# Sheet3.net
KiCad netlist of a schematic drawn in Altium Designer
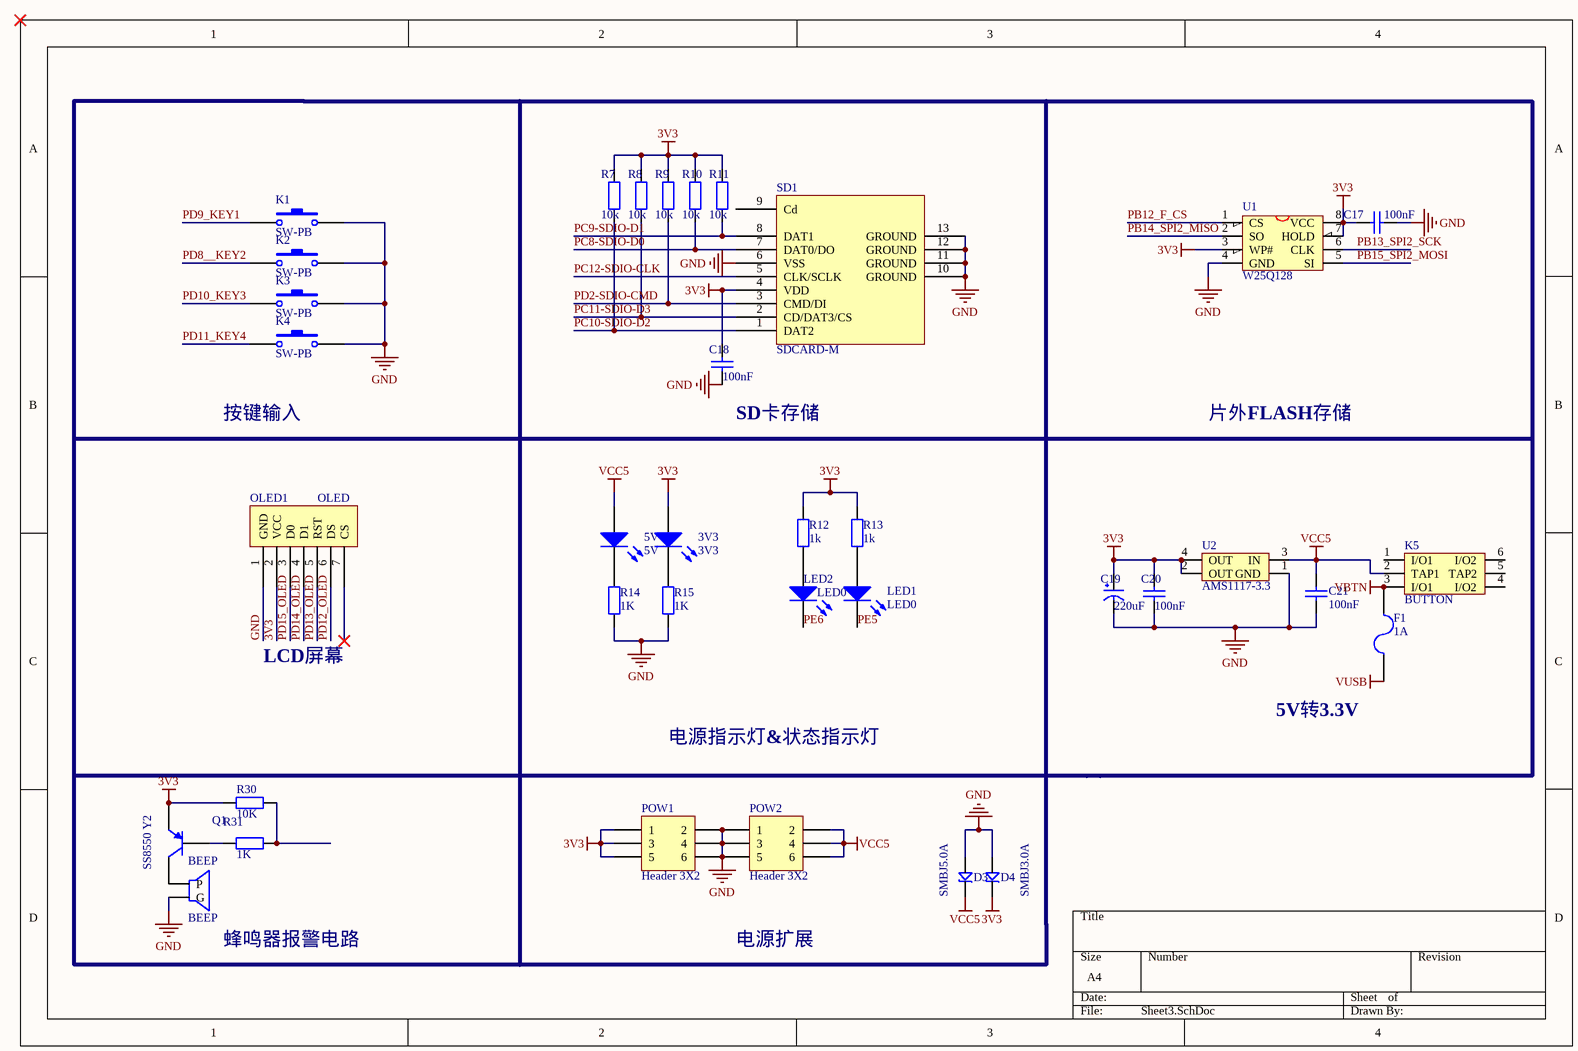
[diagram p0: Sheet3.SchDoc]

(export (version "E")
  (design (tool "Eeschema 10.0.6"))
  (components
    (comp (ref "3V3")
      (value "3V3")
      (footprint "LED_0805")
      (description "Typical INFRARED GaAs LED")
      (fields (field (name "PUBLISHER") "Altium Limited"))
      (libsource (lib "PCB_Project") (part "LED0"))
    )
    (comp (ref "5V")
      (value "5V")
      (footprint "LED_0805")
      (description "Typical INFRARED GaAs LED")
      (fields (field (name "PUBLISHER") "Altium Limited"))
      (libsource (lib "PCB_Project") (part "LED0"))
    )
    (comp (ref "BEEP")
      (value "BEEP")
      (footprint "BUZZER")
      (libsource (lib "Explorer STM32F407封装库") (part "BEEP"))
    )
    (comp (ref "C17")
      (value "100nF")
      (footprint "LC-0603_C")
      (description "无极性电容")
      (fields (field (name "PUBLISHER") "Altium Limited"))
      (libsource (lib "liu_2016") (part "Cap"))
    )
    (comp (ref "C18")
      (value "100nF")
      (footprint "LC-0603_C")
      (description "无极性电容")
      (fields (field (name "PUBLISHER") "Altium Limited"))
      (libsource (lib "liu_2016") (part "Cap"))
    )
    (comp (ref "C19")
      (value "220uF")
      (footprint "CAP_10*10")
      (libsource (lib "Explorer STM32F407封装库") (part "CAP"))
    )
    (comp (ref "C20")
      (value "100nF")
      (footprint "LC-0603_C")
      (description "无极性电容")
      (fields (field (name "PUBLISHER") "Altium Limited"))
      (libsource (lib "liu_2016") (part "Cap"))
    )
    (comp (ref "C21")
      (value "100nF")
      (footprint "LC-0603_C")
      (description "无极性电容")
      (fields (field (name "PUBLISHER") "Altium Limited"))
      (libsource (lib "liu_2016") (part "Cap"))
    )
    (comp (ref "D3")
      (value "SMBJ5.0A")
      (footprint "D1812")
      (description "TVS")
      (libsource (lib "Explorer STM32F407封装库") (part "SMBJ"))
    )
    (comp (ref "D4")
      (value "SMBJ3.0A")
      (footprint "D1812")
      (description "TVS")
      (libsource (lib "Explorer STM32F407封装库") (part "SMBJ"))
    )
    (comp (ref "F1")
      (value "1A")
      (footprint "LC-1206_R")
      (description "保险丝")
      (fields (field (name "Comment") "Fuse") (field (name "PUBLISHER") "Altium Limited"))
      (libsource (lib "liu_2016") (part "Fuse 2"))
    )
    (comp (ref "K1")
      (value "SW-PB")
      (footprint "SW-SMD1")
      (description "Switch")
      (fields (field (name "PUBLISHER") "Altium Limited"))
      (libsource (lib "PCB_Project") (part "SW-PB"))
    )
    (comp (ref "K2")
      (value "SW-PB")
      (footprint "SW-SMD1")
      (description "Switch")
      (fields (field (name "PUBLISHER") "Altium Limited"))
      (libsource (lib "PCB_Project") (part "SW-PB"))
    )
    (comp (ref "K3")
      (value "SW-PB")
      (footprint "SW-SMD1")
      (description "Switch")
      (fields (field (name "PUBLISHER") "Altium Limited"))
      (libsource (lib "PCB_Project") (part "SW-PB"))
    )
    (comp (ref "K4")
      (value "SW-PB")
      (footprint "SW-SMD1")
      (description "Switch")
      (fields (field (name "PUBLISHER") "Altium Limited"))
      (libsource (lib "PCB_Project") (part "SW-PB"))
    )
    (comp (ref "K5")
      (value "BUTTON")
      (footprint "DPDT")
      (libsource (lib "Explorer STM32F407封装库") (part "BUTTON"))
    )
    (comp (ref "LED1")
      (value "LED0")
      (footprint "LED_0805")
      (description "Typical INFRARED GaAs LED")
      (fields (field (name "PUBLISHER") "Altium Limited"))
      (libsource (lib "PCB_Project") (part "LED0"))
    )
    (comp (ref "LED2")
      (value "LED0")
      (footprint "LED_0805")
      (description "Typical INFRARED GaAs LED")
      (fields (field (name "PUBLISHER") "Altium Limited"))
      (libsource (lib "PCB_Project") (part "LED0"))
    )
    (comp (ref "OLED1")
      (value "OLED")
      (footprint "OLED_096")
      (description "OLED屏幕")
      (libsource (lib "liu_2016") (part "OLED_SPI"))
    )
    (comp (ref "POW1")
      (value "Header 3X2")
      (footprint "HDR2X3")
      (description "Header, 3-Pin, Dual row")
      (fields (field (name "PUBLISHER") "Altium Limited"))
      (libsource (lib "Sparks") (part "Header 3X2"))
    )
    (comp (ref "POW2")
      (value "Header 3X2")
      (footprint "HDR2X3")
      (description "Header, 3-Pin, Dual row")
      (fields (field (name "PUBLISHER") "Altium Limited"))
      (libsource (lib "Sparks") (part "Header 3X2"))
    )
    (comp (ref "Q1")
      (value "SS8550 Y2")
      (footprint "LC-SOT-23(SOT-23-3)")
      (description "三极管")
      (libsource (lib "Miscellaneous Devices LC") (part "SOT-23 SS8550 Y2"))
    )
    (comp (ref "R7")
      (value "10k")
      (footprint "LC-0603_R")
      (description "贴片电阻")
      (fields (field (name "PUBLISHER") "Altium Limited"))
      (libsource (lib "liu_2016") (part "Res1"))
    )
    (comp (ref "R8")
      (value "10k")
      (footprint "LC-0603_R")
      (description "贴片电阻")
      (fields (field (name "PUBLISHER") "Altium Limited"))
      (libsource (lib "liu_2016") (part "Res1"))
    )
    (comp (ref "R9")
      (value "10k")
      (footprint "LC-0603_R")
      (description "贴片电阻")
      (fields (field (name "PUBLISHER") "Altium Limited"))
      (libsource (lib "liu_2016") (part "Res1"))
    )
    (comp (ref "R10")
      (value "10k")
      (footprint "LC-0603_R")
      (description "贴片电阻")
      (fields (field (name "PUBLISHER") "Altium Limited"))
      (libsource (lib "liu_2016") (part "Res1"))
    )
    (comp (ref "R11")
      (value "10k")
      (footprint "LC-0603_R")
      (description "贴片电阻")
      (fields (field (name "PUBLISHER") "Altium Limited"))
      (libsource (lib "liu_2016") (part "Res1"))
    )
    (comp (ref "R12")
      (value "1k")
      (footprint "LC-0603_R")
      (description "贴片电阻")
      (fields (field (name "PUBLISHER") "Altium Limited"))
      (libsource (lib "liu_2016") (part "Res1"))
    )
    (comp (ref "R13")
      (value "1k")
      (footprint "LC-0603_R")
      (description "贴片电阻")
      (fields (field (name "PUBLISHER") "Altium Limited"))
      (libsource (lib "liu_2016") (part "Res1"))
    )
    (comp (ref "R14")
      (value "1K")
      (footprint "LC-0603_R")
      (description "贴片电阻")
      (libsource (lib "") (part "0603 1.1KΩ (1101) 1%_1"))
    )
    (comp (ref "R15")
      (value "1K")
      (footprint "LC-0603_R")
      (description "贴片电阻")
      (libsource (lib "") (part "0603 1.1KΩ (1101) 1%_1"))
    )
    (comp (ref "R30")
      (value "10K")
      (footprint "LC-0603_R")
      (description "贴片电阻")
      (libsource (lib "Miscellaneous Devices LC") (part "0603 1.1KΩ (1101) 1%"))
    )
    (comp (ref "R31")
      (value "1K")
      (footprint "LC-0603_R")
      (description "贴片电阻")
      (libsource (lib "Miscellaneous Devices LC") (part "0603 1.1KΩ (1101) 1%"))
    )
    (comp (ref "SD1")
      (value "SDCARD-M")
      (footprint "TF_CARD")
      (description "TF卡槽")
      (libsource (lib "Fszhang") (part "SDCARD-M"))
    )
    (comp (ref "U1")
      (value "W25Q128")
      (footprint "SOIC-8")
      (description "W25X16;SST25VF016;MX25L1605")
      (libsource (lib "SWUST_PanPan") (part "W25X16"))
    )
    (comp (ref "U2")
      (value "AMS1117-3.3")
      (footprint "SOT-233")
      (libsource (lib "Explorer STM32F407封装库") (part "AMS1117"))
    )
  )
  (nets
    (net (code "1") (name "/PB12_F_CS") (class "Default")
      (node (ref "U1") (pin "1") (pinfunction "CS_1") (pintype "passive"))
    )
    (net (code "2") (name "/PB13_SPI2_SCK") (class "Default")
      (node (ref "U1") (pin "6") (pinfunction "CLK_6") (pintype "passive"))
    )
    (net (code "3") (name "/PB14_SPI2_MISO") (class "Default")
      (node (ref "U1") (pin "2") (pinfunction "SO_2") (pintype "passive"))
    )
    (net (code "4") (name "/PB15_SPI2_MOSI") (class "Default")
      (node (ref "U1") (pin "5") (pinfunction "SI_5") (pintype "passive"))
    )
    (net (code "5") (name "/PC8-SDIO-D0") (class "Default")
      (node (ref "R10") (pin "2") (pinfunction "2_2") (pintype "passive"))
      (node (ref "SD1") (pin "7") (pinfunction "DAT0/DO_7") (pintype "passive"))
    )
    (net (code "6") (name "/PC9-SDIO-D1") (class "Default")
      (node (ref "R11") (pin "2") (pinfunction "2_2") (pintype "passive"))
      (node (ref "SD1") (pin "8") (pinfunction "DAT1_8") (pintype "passive"))
    )
    (net (code "7") (name "/PC10-SDIO-D2") (class "Default")
      (node (ref "R7") (pin "2") (pinfunction "2_2") (pintype "passive"))
      (node (ref "SD1") (pin "1") (pinfunction "DAT2_1") (pintype "passive"))
    )
    (net (code "8") (name "/PC11-SDIO-D3") (class "Default")
      (node (ref "R8") (pin "2") (pinfunction "2_2") (pintype "passive"))
      (node (ref "SD1") (pin "2") (pinfunction "CD/DAT3/CS_2") (pintype "passive"))
    )
    (net (code "9") (name "/PC12-SDIO-CLK") (class "Default")
      (node (ref "SD1") (pin "5") (pinfunction "CLK/SCLK_5") (pintype "passive"))
    )
    (net (code "10") (name "/PD2-SDIO-CMD") (class "Default")
      (node (ref "R9") (pin "2") (pinfunction "2_2") (pintype "passive"))
      (node (ref "SD1") (pin "3") (pinfunction "CMD/DI_3") (pintype "passive"))
    )
    (net (code "11") (name "/PD8__KEY2") (class "Default")
      (node (ref "K2") (pin "1") (pinfunction "1_1") (pintype "passive"))
    )
    (net (code "12") (name "/PD9_KEY1") (class "Default")
      (node (ref "K1") (pin "1") (pinfunction "1_1") (pintype "passive"))
    )
    (net (code "13") (name "/PD10_KEY3") (class "Default")
      (node (ref "K3") (pin "1") (pinfunction "1_1") (pintype "passive"))
    )
    (net (code "14") (name "/PD11_KEY4") (class "Default")
      (node (ref "K4") (pin "1") (pinfunction "1_1") (pintype "passive"))
    )
    (net (code "15") (name "/PD12_OLED") (class "Default")
      (node (ref "OLED1") (pin "6") (pinfunction "DS_6") (pintype "passive"))
    )
    (net (code "16") (name "/PD13_OLED") (class "Default")
      (node (ref "OLED1") (pin "5") (pinfunction "RST_5") (pintype "passive"))
    )
    (net (code "17") (name "/PD14_OLED") (class "Default")
      (node (ref "OLED1") (pin "4") (pinfunction "D1_4") (pintype "passive"))
    )
    (net (code "18") (name "/PD15_OLED") (class "Default")
      (node (ref "OLED1") (pin "3") (pinfunction "D0_3") (pintype "passive"))
    )
    (net (code "19") (name "/PE5") (class "Default")
      (node (ref "LED1") (pin "2") (pinfunction "K_2") (pintype "passive"))
    )
    (net (code "20") (name "/PE6") (class "Default")
      (node (ref "LED2") (pin "2") (pinfunction "K_2") (pintype "passive"))
    )
    (net (code "21") (name "3V3") (class "Default")
      (node (ref "3V3") (pin "1") (pinfunction "A_1") (pintype "passive"))
      (node (ref "C17") (pin "2") (pinfunction "2_2") (pintype "passive"))
      (node (ref "C18") (pin "2") (pinfunction "2_2") (pintype "passive"))
      (node (ref "C19") (pin "1") (pinfunction "VCC_1") (pintype "passive"))
      (node (ref "C20") (pin "2") (pinfunction "2_2") (pintype "passive"))
      (node (ref "D4") (pin "2") (pintype "passive"))
      (node (ref "OLED1") (pin "2") (pinfunction "VCC_2") (pintype "passive"))
      (node (ref "POW1") (pin "1") (pinfunction "1_1") (pintype "passive"))
      (node (ref "POW1") (pin "3") (pinfunction "3_3") (pintype "passive"))
      (node (ref "POW1") (pin "5") (pinfunction "5_5") (pintype "passive"))
      (node (ref "Q1") (pin "2") (pinfunction "E_2") (pintype "passive"))
      (node (ref "R10") (pin "1") (pinfunction "1_1") (pintype "passive"))
      (node (ref "R11") (pin "1") (pinfunction "1_1") (pintype "passive"))
      (node (ref "R12") (pin "1") (pinfunction "1_1") (pintype "passive"))
      (node (ref "R13") (pin "1") (pinfunction "1_1") (pintype "passive"))
      (node (ref "R30") (pin "2") (pinfunction "2_2") (pintype "passive"))
      (node (ref "R7") (pin "1") (pinfunction "1_1") (pintype "passive"))
      (node (ref "R8") (pin "1") (pinfunction "1_1") (pintype "passive"))
      (node (ref "R9") (pin "1") (pinfunction "1_1") (pintype "passive"))
      (node (ref "SD1") (pin "4") (pinfunction "VDD_4") (pintype "passive"))
      (node (ref "U1") (pin "3") (pinfunction "WP#_3") (pintype "passive"))
      (node (ref "U1") (pin "7") (pinfunction "HOLD_7") (pintype "passive"))
      (node (ref "U1") (pin "8") (pinfunction "VCC_8") (pintype "passive"))
      (node (ref "U2") (pin "2") (pinfunction "OUT_2") (pintype "passive"))
      (node (ref "U2") (pin "4") (pinfunction "OUT_4") (pintype "passive"))
    )
    (net (code "22") (name "GND") (class "Default")
      (node (ref "BEEP") (pin "2") (pinfunction "G_2") (pintype "passive"))
      (node (ref "C17") (pin "1") (pinfunction "1_1") (pintype "passive"))
      (node (ref "C18") (pin "1") (pinfunction "1_1") (pintype "passive"))
      (node (ref "C19") (pin "2") (pinfunction "GND_2") (pintype "passive"))
      (node (ref "C20") (pin "1") (pinfunction "1_1") (pintype "passive"))
      (node (ref "C21") (pin "1") (pinfunction "1_1") (pintype "passive"))
      (node (ref "D3") (pin "1") (pintype "passive"))
      (node (ref "D4") (pin "1") (pintype "passive"))
      (node (ref "K1") (pin "2") (pinfunction "2_2") (pintype "passive"))
      (node (ref "K2") (pin "2") (pinfunction "2_2") (pintype "passive"))
      (node (ref "K3") (pin "2") (pinfunction "2_2") (pintype "passive"))
      (node (ref "K4") (pin "2") (pinfunction "2_2") (pintype "passive"))
      (node (ref "OLED1") (pin "1") (pinfunction "GND_1") (pintype "passive"))
      (node (ref "POW1") (pin "2") (pinfunction "2_2") (pintype "passive"))
      (node (ref "POW1") (pin "4") (pinfunction "4_4") (pintype "passive"))
      (node (ref "POW1") (pin "6") (pinfunction "6_6") (pintype "passive"))
      (node (ref "POW2") (pin "1") (pinfunction "1_1") (pintype "passive"))
      (node (ref "POW2") (pin "3") (pinfunction "3_3") (pintype "passive"))
      (node (ref "POW2") (pin "5") (pinfunction "5_5") (pintype "passive"))
      (node (ref "R14") (pin "1") (pinfunction "1_1") (pintype "passive"))
      (node (ref "R15") (pin "1") (pinfunction "1_1") (pintype "passive"))
      (node (ref "SD1") (pin "10") (pinfunction "GROUND_10") (pintype "passive"))
      (node (ref "SD1") (pin "11") (pinfunction "GROUND_11") (pintype "passive"))
      (node (ref "SD1") (pin "12") (pinfunction "GROUND_12") (pintype "passive"))
      (node (ref "SD1") (pin "13") (pinfunction "GROUND_13") (pintype "passive"))
      (node (ref "SD1") (pin "6") (pinfunction "VSS_6") (pintype "passive"))
      (node (ref "U1") (pin "4") (pinfunction "GND_4") (pintype "passive"))
      (node (ref "U2") (pin "1") (pinfunction "GND_1") (pintype "passive"))
    )
    (net (code "23") (name "Net-(3V3-K)") (class "Default")
      (node (ref "3V3") (pin "2") (pinfunction "K_2") (pintype "passive"))
      (node (ref "R15") (pin "2") (pinfunction "2_2") (pintype "passive"))
    )
    (net (code "24") (name "Net-(5V-K)") (class "Default")
      (node (ref "5V") (pin "2") (pinfunction "K_2") (pintype "passive"))
      (node (ref "R14") (pin "2") (pinfunction "2_2") (pintype "passive"))
    )
    (net (code "25") (name "Net-(BEEP-P)") (class "Default")
      (node (ref "BEEP") (pin "1") (pinfunction "P_1") (pintype "passive"))
      (node (ref "Q1") (pin "3") (pinfunction "C_3") (pintype "passive"))
    )
    (net (code "26") (name "Net-(LED1-A)") (class "Default")
      (node (ref "LED1") (pin "1") (pinfunction "A_1") (pintype "passive"))
      (node (ref "R13") (pin "2") (pinfunction "2_2") (pintype "passive"))
    )
    (net (code "27") (name "Net-(LED2-A)") (class "Default")
      (node (ref "LED2") (pin "1") (pinfunction "A_1") (pintype "passive"))
      (node (ref "R12") (pin "2") (pinfunction "2_2") (pintype "passive"))
    )
    (net (code "28") (name "Net-(Q1-B)") (class "Default")
      (node (ref "Q1") (pin "1") (pinfunction "B_1") (pintype "passive"))
      (node (ref "R31") (pin "2") (pinfunction "2_2") (pintype "passive"))
    )
    (net (code "29") (name "Net-(R30-Pad1)") (class "Default")
      (node (ref "R30") (pin "1") (pinfunction "1_1") (pintype "passive"))
      (node (ref "R31") (pin "1") (pinfunction "1_1") (pintype "passive"))
    )
    (net (code "30") (name "VBTN") (class "Default")
      (node (ref "F1") (pin "2") (pinfunction "2_2") (pintype "passive"))
      (node (ref "K5") (pin "3") (pinfunction "I/O1_3") (pintype "passive"))
    )
    (net (code "31") (name "VCC5") (class "Default")
      (node (ref "5V") (pin "1") (pinfunction "A_1") (pintype "passive"))
      (node (ref "C21") (pin "2") (pinfunction "2_2") (pintype "passive"))
      (node (ref "D3") (pin "2") (pintype "passive"))
      (node (ref "K5") (pin "2") (pinfunction "TAP1_2") (pintype "passive"))
      (node (ref "POW2") (pin "2") (pinfunction "2_2") (pintype "passive"))
      (node (ref "POW2") (pin "4") (pinfunction "4_4") (pintype "passive"))
      (node (ref "POW2") (pin "6") (pinfunction "6_6") (pintype "passive"))
      (node (ref "U2") (pin "3") (pinfunction "IN_3") (pintype "passive"))
    )
    (net (code "32") (name "VUSB") (class "Default")
      (node (ref "F1") (pin "1") (pinfunction "1_1") (pintype "passive"))
    )
    (net (code "33") (name "unconnected-(K5-I{slash}O1-Pad1)") (class "Default")
      (node (ref "K5") (pin "1") (pinfunction "I/O1_1") (pintype "passive"))
    )
    (net (code "34") (name "unconnected-(K5-I{slash}O2-Pad4)") (class "Default")
      (node (ref "K5") (pin "4") (pinfunction "I/O2_4") (pintype "passive"))
    )
    (net (code "35") (name "unconnected-(K5-I{slash}O2-Pad6)") (class "Default")
      (node (ref "K5") (pin "6") (pinfunction "I/O2_6") (pintype "passive"))
    )
    (net (code "36") (name "unconnected-(K5-TAP2-Pad5)") (class "Default")
      (node (ref "K5") (pin "5") (pinfunction "TAP2_5") (pintype "passive"))
    )
    (net (code "37") (name "unconnected-(OLED1-CS-Pad7)") (class "Default")
      (node (ref "OLED1") (pin "7") (pinfunction "CS_7") (pintype "passive+no_connect"))
    )
    (net (code "38") (name "unconnected-(SD1-Cd-Pad9)") (class "Default")
      (node (ref "SD1") (pin "9") (pinfunction "Cd_9") (pintype "passive"))
    )
  )
)
